# V_9.net
KiCad netlist of a schematic drawn in Altium Designer
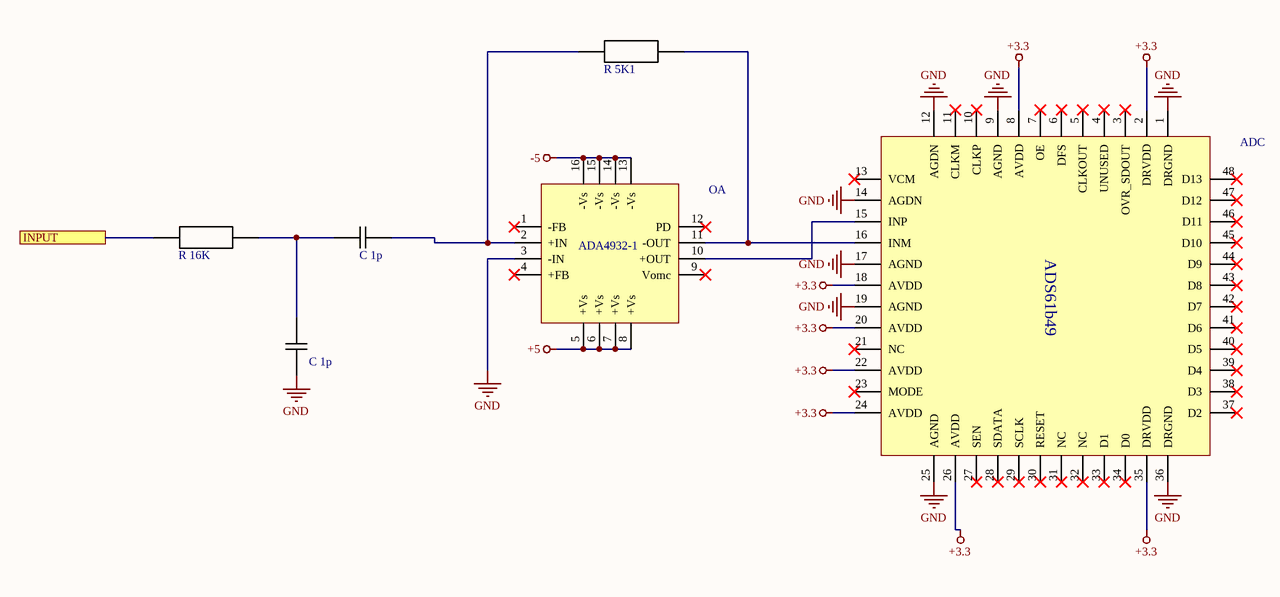
[diagram p0: V_9.SchDoc]

(export (version "E")
  (design (tool "Eeschema 10.0.6"))
  (components
    (comp (ref "1")
      (value "ADC")
      (footprint "PcbLib1:ADS61B49")
      (libsource (lib "altium-import") (part "root_3_ADC_"))
    )
    (comp (ref "2") (value "OA") (footprint "PcbLib1:ADA4932-1") (libsource (lib "Schlib1") (part "OA")))
    (comp (ref "3")
      (value "R 16K")
      (footprint "PcbLib1:R0805")
      (description "16K")
      (libsource (lib "altium-import") (part "root_0_R_"))
    )
    (comp (ref "4")
      (value "C 1p")
      (footprint "PcbLib1:С0805")
      (libsource (lib "altium-import") (part "root_0_C_"))
    )
    (comp (ref "8")
      (value "C 1p")
      (footprint "PcbLib1:С0805")
      (libsource (lib "altium-import") (part "root_1_C_"))
    )
    (comp (ref "9")
      (value "R 5K1")
      (footprint "PcbLib1:R0805")
      (libsource (lib "altium-import") (part "root_0_R_"))
    )
  )
  (nets
    (net (code "1") (name "+3.3") (class "Default")
      (node (ref "1") (pin "18") (pinfunction "AVDD_18") (pintype "passive"))
      (node (ref "1") (pin "2") (pinfunction "DRVDD_2") (pintype "passive"))
      (node (ref "1") (pin "20") (pinfunction "AVDD_20") (pintype "passive"))
      (node (ref "1") (pin "22") (pinfunction "AVDD_22") (pintype "passive"))
      (node (ref "1") (pin "24") (pinfunction "AVDD_24") (pintype "passive"))
      (node (ref "1") (pin "26") (pinfunction "AVDD_26") (pintype "passive"))
      (node (ref "1") (pin "35") (pinfunction "DRVDD_35") (pintype "passive"))
      (node (ref "1") (pin "8") (pinfunction "AVDD_8") (pintype "passive"))
    )
    (net (code "2") (name "+5") (class "Default")
      (node (ref "2") (pin "5") (pinfunction "+Vs_5") (pintype "passive"))
      (node (ref "2") (pin "6") (pinfunction "+Vs_6") (pintype "passive"))
      (node (ref "2") (pin "7") (pinfunction "+Vs_7") (pintype "passive"))
      (node (ref "2") (pin "8") (pinfunction "+Vs_8") (pintype "passive"))
    )
    (net (code "3") (name "-5") (class "Default")
      (node (ref "2") (pin "13") (pinfunction "-Vs_13") (pintype "passive"))
      (node (ref "2") (pin "14") (pinfunction "-Vs_14") (pintype "passive"))
      (node (ref "2") (pin "15") (pinfunction "-Vs_15") (pintype "passive"))
      (node (ref "2") (pin "16") (pinfunction "-Vs_16") (pintype "passive"))
    )
    (net (code "4") (name "/INPUT") (class "Default")
      (node (ref "3") (pin "1") (pinfunction "1_1") (pintype "passive"))
    )
    (net (code "5") (name "GND") (class "Default")
      (node (ref "1") (pin "1") (pinfunction "DRGND_1") (pintype "passive"))
      (node (ref "1") (pin "12") (pinfunction "AGDN_12") (pintype "passive"))
      (node (ref "1") (pin "14") (pinfunction "AGDN_14") (pintype "passive"))
      (node (ref "1") (pin "17") (pinfunction "AGND_17") (pintype "passive"))
      (node (ref "1") (pin "19") (pinfunction "AGND_19") (pintype "passive"))
      (node (ref "1") (pin "25") (pinfunction "AGND_25") (pintype "passive"))
      (node (ref "1") (pin "36") (pinfunction "DRGND_36") (pintype "passive"))
      (node (ref "1") (pin "9") (pinfunction "AGND_9") (pintype "passive"))
      (node (ref "2") (pin "3") (pinfunction "-IN_3") (pintype "passive"))
      (node (ref "8") (pin "1") (pinfunction "1_1") (pintype "passive"))
    )
    (net (code "6") (name "Net-(1-INM)") (class "Default")
      (node (ref "1") (pin "16") (pinfunction "INM_16") (pintype "passive"))
      (node (ref "2") (pin "11") (pinfunction "-OUT_11") (pintype "passive"))
      (node (ref "9") (pin "2") (pinfunction "2_2") (pintype "passive"))
    )
    (net (code "7") (name "Net-(1-INP)") (class "Default")
      (node (ref "1") (pin "15") (pinfunction "INP_15") (pintype "passive"))
      (node (ref "2") (pin "10") (pinfunction "+OUT_10") (pintype "passive"))
    )
    (net (code "8") (name "Net-(2-+IN)") (class "Default")
      (node (ref "2") (pin "2") (pinfunction "+IN_2") (pintype "passive"))
      (node (ref "4") (pin "2") (pinfunction "2_2") (pintype "passive"))
      (node (ref "9") (pin "1") (pinfunction "1_1") (pintype "passive"))
    )
    (net (code "9") (name "Net-(3-Pad2)") (class "Default")
      (node (ref "3") (pin "2") (pinfunction "2_2") (pintype "passive"))
      (node (ref "4") (pin "1") (pinfunction "1_1") (pintype "passive"))
      (node (ref "8") (pin "2") (pinfunction "2_2") (pintype "passive"))
    )
    (net (code "10") (name "unconnected-(1-CLKM-Pad11)") (class "Default")
      (node (ref "1") (pin "11") (pinfunction "CLKM_11") (pintype "passive+no_connect"))
    )
    (net (code "11") (name "unconnected-(1-CLKOUT-Pad5)") (class "Default")
      (node (ref "1") (pin "5") (pinfunction "CLKOUT_5") (pintype "passive+no_connect"))
    )
    (net (code "12") (name "unconnected-(1-CLKP-Pad10)") (class "Default")
      (node (ref "1") (pin "10") (pinfunction "CLKP_10") (pintype "passive+no_connect"))
    )
    (net (code "13") (name "unconnected-(1-D0-Pad34)") (class "Default")
      (node (ref "1") (pin "34") (pinfunction "D0_34") (pintype "passive+no_connect"))
    )
    (net (code "14") (name "unconnected-(1-D1-Pad33)") (class "Default")
      (node (ref "1") (pin "33") (pinfunction "D1_33") (pintype "passive+no_connect"))
    )
    (net (code "15") (name "unconnected-(1-D2-Pad37)") (class "Default")
      (node (ref "1") (pin "37") (pinfunction "D2_37") (pintype "passive+no_connect"))
    )
    (net (code "16") (name "unconnected-(1-D3-Pad38)") (class "Default")
      (node (ref "1") (pin "38") (pinfunction "D3_38") (pintype "passive+no_connect"))
    )
    (net (code "17") (name "unconnected-(1-D4-Pad39)") (class "Default")
      (node (ref "1") (pin "39") (pinfunction "D4_39") (pintype "passive+no_connect"))
    )
    (net (code "18") (name "unconnected-(1-D5-Pad40)") (class "Default")
      (node (ref "1") (pin "40") (pinfunction "D5_40") (pintype "passive+no_connect"))
    )
    (net (code "19") (name "unconnected-(1-D6-Pad41)") (class "Default")
      (node (ref "1") (pin "41") (pinfunction "D6_41") (pintype "passive+no_connect"))
    )
    (net (code "20") (name "unconnected-(1-D7-Pad42)") (class "Default")
      (node (ref "1") (pin "42") (pinfunction "D7_42") (pintype "passive+no_connect"))
    )
    (net (code "21") (name "unconnected-(1-D8-Pad43)") (class "Default")
      (node (ref "1") (pin "43") (pinfunction "D8_43") (pintype "passive+no_connect"))
    )
    (net (code "22") (name "unconnected-(1-D9-Pad44)") (class "Default")
      (node (ref "1") (pin "44") (pinfunction "D9_44") (pintype "passive+no_connect"))
    )
    (net (code "23") (name "unconnected-(1-D10-Pad45)") (class "Default")
      (node (ref "1") (pin "45") (pinfunction "D10_45") (pintype "passive+no_connect"))
    )
    (net (code "24") (name "unconnected-(1-D11-Pad46)") (class "Default")
      (node (ref "1") (pin "46") (pinfunction "D11_46") (pintype "passive+no_connect"))
    )
    (net (code "25") (name "unconnected-(1-D12-Pad47)") (class "Default")
      (node (ref "1") (pin "47") (pinfunction "D12_47") (pintype "passive+no_connect"))
    )
    (net (code "26") (name "unconnected-(1-D13-Pad48)") (class "Default")
      (node (ref "1") (pin "48") (pinfunction "D13_48") (pintype "passive+no_connect"))
    )
    (net (code "27") (name "unconnected-(1-DFS-Pad6)") (class "Default")
      (node (ref "1") (pin "6") (pinfunction "DFS_6") (pintype "passive+no_connect"))
    )
    (net (code "28") (name "unconnected-(1-MODE-Pad23)") (class "Default")
      (node (ref "1") (pin "23") (pinfunction "MODE_23") (pintype "passive+no_connect"))
    )
    (net (code "29") (name "unconnected-(1-NC-Pad21)") (class "Default")
      (node (ref "1") (pin "21") (pinfunction "NC_21") (pintype "passive+no_connect"))
    )
    (net (code "30") (name "unconnected-(1-NC-Pad31)") (class "Default")
      (node (ref "1") (pin "31") (pinfunction "NC_31") (pintype "passive+no_connect"))
    )
    (net (code "31") (name "unconnected-(1-NC-Pad32)") (class "Default")
      (node (ref "1") (pin "32") (pinfunction "NC_32") (pintype "passive+no_connect"))
    )
    (net (code "32") (name "unconnected-(1-OE-Pad7)") (class "Default")
      (node (ref "1") (pin "7") (pinfunction "OE_7") (pintype "passive+no_connect"))
    )
    (net (code "33") (name "unconnected-(1-OVR_SDOUT-Pad3)") (class "Default")
      (node (ref "1") (pin "3") (pinfunction "OVR_SDOUT_3") (pintype "passive+no_connect"))
    )
    (net (code "34") (name "unconnected-(1-RESET-Pad30)") (class "Default")
      (node (ref "1") (pin "30") (pinfunction "RESET_30") (pintype "passive+no_connect"))
    )
    (net (code "35") (name "unconnected-(1-SCLK-Pad29)") (class "Default")
      (node (ref "1") (pin "29") (pinfunction "SCLK_29") (pintype "passive+no_connect"))
    )
    (net (code "36") (name "unconnected-(1-SDATA-Pad28)") (class "Default")
      (node (ref "1") (pin "28") (pinfunction "SDATA_28") (pintype "passive+no_connect"))
    )
    (net (code "37") (name "unconnected-(1-SEN-Pad27)") (class "Default")
      (node (ref "1") (pin "27") (pinfunction "SEN_27") (pintype "passive+no_connect"))
    )
    (net (code "38") (name "unconnected-(1-UNUSED-Pad4)") (class "Default")
      (node (ref "1") (pin "4") (pinfunction "UNUSED_4") (pintype "passive+no_connect"))
    )
    (net (code "39") (name "unconnected-(1-VCM-Pad13)") (class "Default")
      (node (ref "1") (pin "13") (pinfunction "VCM_13") (pintype "passive+no_connect"))
    )
    (net (code "40") (name "unconnected-(2-+FB-Pad4)") (class "Default")
      (node (ref "2") (pin "4") (pinfunction "+FB_4") (pintype "passive+no_connect"))
    )
    (net (code "41") (name "unconnected-(2--FB-Pad1)") (class "Default")
      (node (ref "2") (pin "1") (pinfunction "-FB_1") (pintype "passive+no_connect"))
    )
    (net (code "42") (name "unconnected-(2-PD-Pad12)") (class "Default")
      (node (ref "2") (pin "12") (pinfunction "PD_12") (pintype "passive+no_connect"))
    )
    (net (code "43") (name "unconnected-(2-Vomc-Pad9)") (class "Default")
      (node (ref "2") (pin "9") (pinfunction "Vomc_9") (pintype "passive+no_connect"))
    )
  )
)
